# V0p2_Main_PCB2.net
KiCad netlist of a schematic drawn in EAGLE
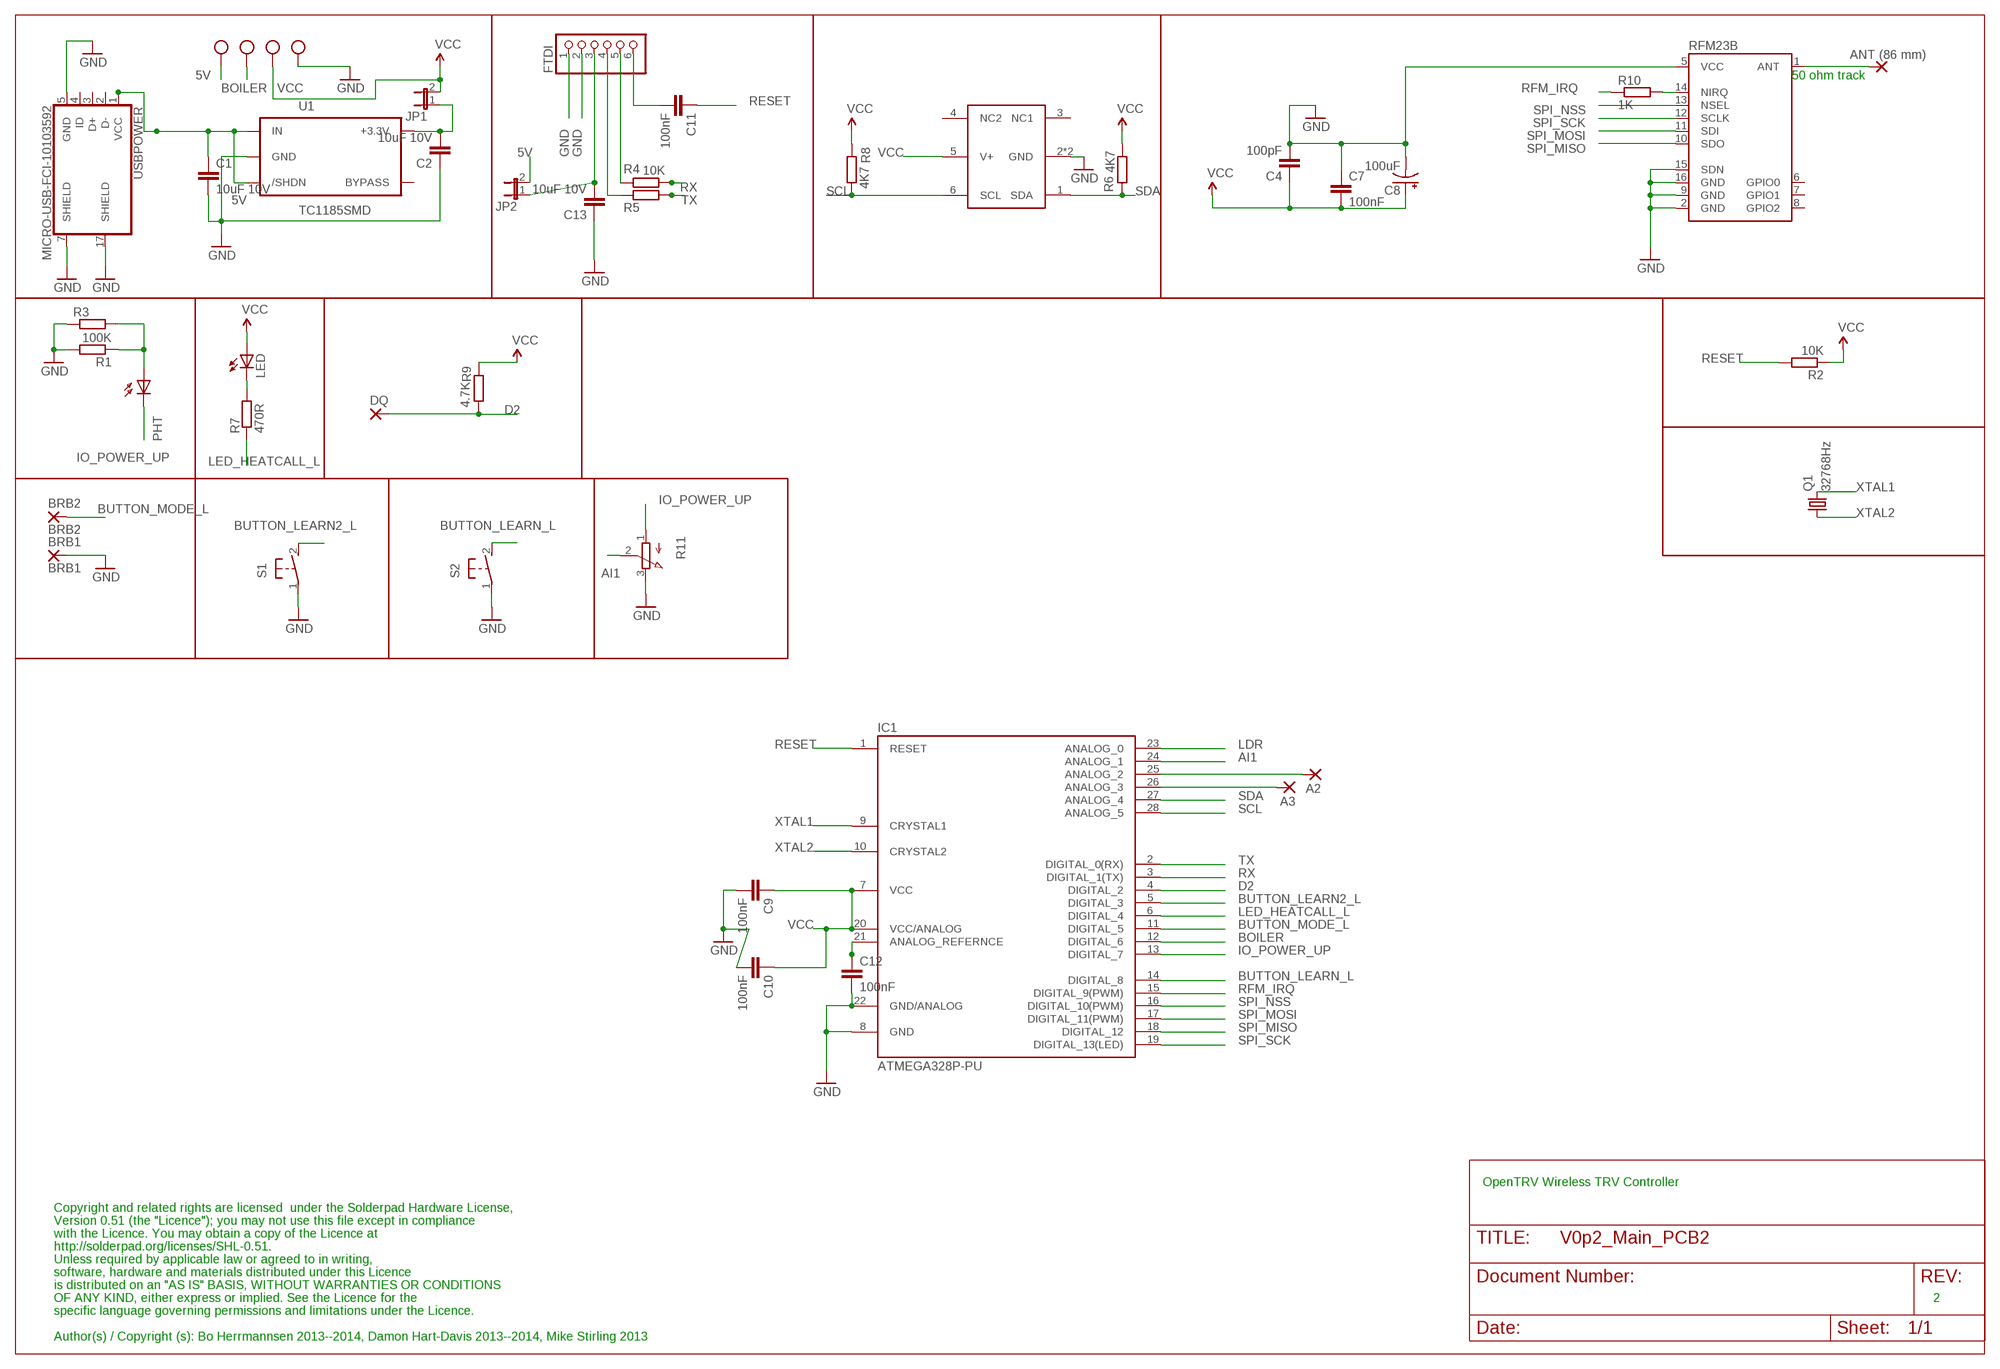
[diagram p0: schematic, sheet 1]

(export (version "E")
  (design (tool "Eeschema 10.0.6"))
  (components
    (comp (ref "A2")
      (value "2,15/1,0")
      (footprint "eagle-import:2,15_1,0")
      (libsource (lib "eagle-import") (part "2,15/1,0"))
    )
    (comp (ref "A3")
      (value "2,15/1,0")
      (footprint "eagle-import:2,15_1,0")
      (libsource (lib "eagle-import") (part "2,15/1,0"))
    )
    (comp (ref "ANT1")
      (value "ANT (86 mm)")
      (footprint "eagle-import:2,15_1,0")
      (libsource (lib "eagle-import") (part "2,15/1,0"))
    )
    (comp (ref "BRB1")
      (value "BRB1")
      (footprint "eagle-import:2,15_1,0")
      (libsource (lib "eagle-import") (part "2,15/1,0"))
    )
    (comp (ref "BRB2")
      (value "BRB2")
      (footprint "eagle-import:2,15_1,0")
      (libsource (lib "eagle-import") (part "2,15/1,0"))
    )
    (comp (ref "C1")
      (value "10uF 10V")
      (footprint "eagle-import:C0603")
      (libsource (lib "eagle-import") (part "C-EUC0603"))
    )
    (comp (ref "C2")
      (value "10uF 10V")
      (footprint "eagle-import:C0603")
      (libsource (lib "eagle-import") (part "C-EUC0603"))
    )
    (comp (ref "C4")
      (value "100pF")
      (footprint "eagle-import:C0603")
      (libsource (lib "eagle-import") (part "C-EUC0603"))
    )
    (comp (ref "C7")
      (value "100nF")
      (footprint "eagle-import:C0603")
      (libsource (lib "eagle-import") (part "C-EUC0603"))
    )
    (comp (ref "C8")
      (value "100uF")
      (footprint "eagle-import:EIA3216")
      (libsource (lib "eagle-import") (part "CAP_POL1206"))
    )
    (comp (ref "C9")
      (value "100nF")
      (footprint "eagle-import:C0603")
      (libsource (lib "eagle-import") (part "C-EUC0603"))
    )
    (comp (ref "C10")
      (value "100nF")
      (footprint "eagle-import:C0603")
      (libsource (lib "eagle-import") (part "C-EUC0603"))
    )
    (comp (ref "C11")
      (value "100nF")
      (footprint "eagle-import:C0603")
      (libsource (lib "eagle-import") (part "C-EUC0603"))
    )
    (comp (ref "C12")
      (value "100nF")
      (footprint "eagle-import:C0603")
      (libsource (lib "eagle-import") (part "C-EUC0603"))
    )
    (comp (ref "C13")
      (value "10uF 10V")
      (footprint "eagle-import:C0603")
      (libsource (lib "eagle-import") (part "C-EUC0603"))
    )
    (comp (ref "DQ")
      (value "2,15/1,0")
      (footprint "eagle-import:2,15_1,0")
      (libsource (lib "eagle-import") (part "2,15/1,0"))
    )
    (comp (ref "FTDI")
      (value "PINHD-1X6/90")
      (footprint "eagle-import:1X06_90")
      (libsource (lib "eagle-import") (part "PINHD-1X6/90"))
    )
    (comp (ref "IC1")
      (value "ATMEGA328P-PU")
      (footprint "eagle-import:DIL28-3")
      (libsource (lib "eagle-import") (part "ATMEGA8-PU"))
    )
    (comp (ref "JP1")
      (value "JP1E")
      (footprint "eagle-import:JP1")
      (libsource (lib "eagle-import") (part "JP1E"))
    )
    (comp (ref "JP2")
      (value "JP1E")
      (footprint "eagle-import:JP1")
      (libsource (lib "eagle-import") (part "JP1E"))
    )
    (comp (ref "LED")
      (value "LED3MM")
      (footprint "eagle-import:LED3MM")
      (libsource (lib "eagle-import") (part "LED3MM"))
    )
    (comp (ref "PHT")
      (value "BPX65")
      (footprint "eagle-import:BPX65")
      (fields (field (name "MPN") "BPX65."))
      (libsource (lib "eagle-import") (part "BPX65"))
    )
    (comp (ref "Q1")
      (value "32768Hz")
      (footprint "eagle-import:MC-306")
      (fields (field (name "MPN") "MC-306 60.0KHZ  100PPM ,12.5PF"))
      (libsource (lib "eagle-import") (part "MC-306"))
    )
    (comp (ref "R1")
      (value "100K")
      (footprint "eagle-import:R0603")
      (libsource (lib "eagle-import") (part "R-EU_R0603"))
    )
    (comp (ref "R2")
      (value "10K")
      (footprint "eagle-import:R0603")
      (libsource (lib "eagle-import") (part "R-EU_R0603"))
    )
    (comp (ref "R3")
      (value "R-EU_0309/V")
      (footprint "eagle-import:0309V")
      (libsource (lib "eagle-import") (part "R-EU_0309/V"))
    )
    (comp (ref "R4")
      (value "10K")
      (footprint "eagle-import:R0603")
      (libsource (lib "eagle-import") (part "R-EU_R0603"))
    )
    (comp (ref "R5")
      (value "10K")
      (footprint "eagle-import:R0603")
      (libsource (lib "eagle-import") (part "R-EU_R0603"))
    )
    (comp (ref "R6")
      (value "4K7")
      (footprint "eagle-import:R0603")
      (libsource (lib "eagle-import") (part "R-EU_R0603"))
    )
    (comp (ref "R7")
      (value "470R")
      (footprint "eagle-import:R0603")
      (libsource (lib "eagle-import") (part "R-EU_R0603"))
    )
    (comp (ref "R8")
      (value "4K7")
      (footprint "eagle-import:R0603")
      (libsource (lib "eagle-import") (part "R-EU_R0603"))
    )
    (comp (ref "R9")
      (value "4.7K")
      (footprint "eagle-import:R0603")
      (libsource (lib "eagle-import") (part "R-EU_R0603"))
    )
    (comp (ref "R10")
      (value "1K")
      (footprint "eagle-import:R0603")
      (libsource (lib "eagle-import") (part "R-EU_R0603"))
    )
    (comp (ref "R11")
      (value "EVUE2A")
      (footprint "eagle-import:EVUE")
      (libsource (lib "eagle-import") (part "EVUE2A"))
    )
    (comp (ref "RFM23B")
      (value "RFM23B")
      (footprint "eagle-import:RFM23-XXX-S1")
      (libsource (lib "eagle-import") (part "RFM23B"))
    )
    (comp (ref "S1")
      (value "31-XX")
      (footprint "eagle-import:B3F-31XX")
      (libsource (lib "eagle-import") (part "31-XX"))
    )
    (comp (ref "S2")
      (value "31-XX")
      (footprint "eagle-import:B3F-31XX")
      (libsource (lib "eagle-import") (part "31-XX"))
    )
    (comp (ref "U$4")
      (value "SHT21")
      (footprint "eagle-import:SHT21")
      (libsource (lib "eagle-import") (part "SHT21"))
    )
    (comp (ref "U1")
      (value "TC1185SMD")
      (footprint "eagle-import:TC1185")
      (libsource (lib "eagle-import") (part "TC1185SMD"))
    )
    (comp (ref "USBPOWER")
      (value "MICRO-USB-FCI-10103592")
      (footprint "eagle-import:MICRO-USB-FCI-10103592")
      (libsource (lib "eagle-import") (part "MICRO-USB-FCI-10103592"))
    )
    (comp (ref "X1")
      (value "W237-102")
      (footprint "eagle-import:SCREWTERMINAL")
      (fields (field (name "MPN") "237-102"))
      (libsource (lib "eagle-import") (part "W237-102"))
    )
    (comp (ref "X2")
      (value "W237-102")
      (footprint "eagle-import:SCREWTERMINAL")
      (fields (field (name "MPN") "237-102"))
      (libsource (lib "eagle-import") (part "W237-102"))
    )
  )
  (nets
    (net (code "1") (name "/5V") (class "Default")
      (node (ref "C1") (pin "1") (pinfunction "1_1") (pintype "passive"))
      (node (ref "JP2") (pin "2") (pinfunction "2_2") (pintype "passive"))
      (node (ref "U1") (pin "1") (pinfunction "IN_1") (pintype "passive"))
      (node (ref "U1") (pin "3") (pinfunction "/SHDN_3") (pintype "passive"))
      (node (ref "USBPOWER") (pin "1") (pinfunction "VCC_1") (pintype "bidirectional"))
      (node (ref "X1") (pin "2") (pinfunction "KL_2") (pintype "passive"))
    )
    (net (code "2") (name "/AI1") (class "Default")
      (node (ref "IC1") (pin "24") (pinfunction "ANALOG_1_24") (pintype "bidirectional"))
      (node (ref "R11") (pin "2") (pinfunction "S_2") (pintype "passive"))
    )
    (net (code "3") (name "/BOILER") (class "Default")
      (node (ref "IC1") (pin "12") (pinfunction "DIGITAL_6_12") (pintype "bidirectional"))
      (node (ref "X1") (pin "1") (pinfunction "KL_1") (pintype "passive"))
    )
    (net (code "4") (name "/BUTTON_LEARN2_L") (class "Default")
      (node (ref "IC1") (pin "5") (pinfunction "DIGITAL_3_5") (pintype "bidirectional"))
      (node (ref "S1") (pin "2") (pinfunction "S_2") (pintype "passive"))
    )
    (net (code "5") (name "/BUTTON_LEARN_L") (class "Default")
      (node (ref "IC1") (pin "14") (pinfunction "DIGITAL_8_14") (pintype "bidirectional"))
      (node (ref "S2") (pin "2") (pinfunction "S_2") (pintype "passive"))
    )
    (net (code "6") (name "/BUTTON_MODE_L") (class "Default")
      (node (ref "BRB2") (pin "1") (pinfunction "P_1") (pintype "passive"))
      (node (ref "IC1") (pin "11") (pinfunction "DIGITAL_5_11") (pintype "bidirectional"))
    )
    (net (code "7") (name "/D2") (class "Default")
      (node (ref "DQ") (pin "1") (pinfunction "P_1") (pintype "passive"))
      (node (ref "IC1") (pin "4") (pinfunction "DIGITAL_2_4") (pintype "bidirectional"))
      (node (ref "R9") (pin "1") (pinfunction "1_1") (pintype "passive"))
    )
    (net (code "8") (name "/IO_POWER_UP") (class "Default")
      (node (ref "IC1") (pin "13") (pinfunction "DIGITAL_7_13") (pintype "bidirectional"))
      (node (ref "PHT") (pin "K") (pinfunction "C_K") (pintype "passive"))
      (node (ref "R11") (pin "1") (pinfunction "A_1") (pintype "passive"))
    )
    (net (code "9") (name "/LDR") (class "Default")
      (node (ref "IC1") (pin "23") (pinfunction "ANALOG_0_23") (pintype "bidirectional"))
      (node (ref "PHT") (pin "A") (pinfunction "A_A") (pintype "passive"))
      (node (ref "R1") (pin "1") (pinfunction "1_1") (pintype "passive"))
      (node (ref "R3") (pin "2") (pinfunction "2_2") (pintype "passive"))
    )
    (net (code "10") (name "/LED_HEATCALL_L") (class "Default")
      (node (ref "IC1") (pin "6") (pinfunction "DIGITAL_4_6") (pintype "bidirectional"))
      (node (ref "R7") (pin "1") (pinfunction "1_1") (pintype "passive"))
    )
    (net (code "11") (name "/RESET") (class "Default")
      (node (ref "C11") (pin "1") (pinfunction "1_1") (pintype "passive"))
      (node (ref "IC1") (pin "1") (pinfunction "RESET_1") (pintype "bidirectional"))
      (node (ref "R2") (pin "2") (pinfunction "2_2") (pintype "passive"))
    )
    (net (code "12") (name "/RFM_IRQ") (class "Default")
      (node (ref "IC1") (pin "15") (pinfunction "DIGITAL_9(PWM)_15") (pintype "bidirectional"))
      (node (ref "R10") (pin "1") (pinfunction "1_1") (pintype "passive"))
    )
    (net (code "13") (name "/RX") (class "Default")
      (node (ref "IC1") (pin "3") (pinfunction "DIGITAL_1(TX)_3") (pintype "bidirectional"))
      (node (ref "R4") (pin "1") (pinfunction "1_1") (pintype "passive"))
    )
    (net (code "14") (name "/SCL") (class "Default")
      (node (ref "IC1") (pin "28") (pinfunction "ANALOG_5_28") (pintype "bidirectional"))
      (node (ref "R8") (pin "1") (pinfunction "1_1") (pintype "passive"))
      (node (ref "U$4") (pin "6") (pinfunction "SCL_6") (pintype "bidirectional"))
    )
    (net (code "15") (name "/SDA") (class "Default")
      (node (ref "IC1") (pin "27") (pinfunction "ANALOG_4_27") (pintype "bidirectional"))
      (node (ref "R6") (pin "2") (pinfunction "2_2") (pintype "passive"))
      (node (ref "U$4") (pin "1") (pinfunction "SDA_1") (pintype "bidirectional"))
    )
    (net (code "16") (name "/SPI_MISO") (class "Default")
      (node (ref "IC1") (pin "18") (pinfunction "DIGITAL_12_18") (pintype "bidirectional"))
      (node (ref "RFM23B") (pin "10") (pinfunction "SDO_10") (pintype "output"))
    )
    (net (code "17") (name "/SPI_MOSI") (class "Default")
      (node (ref "IC1") (pin "17") (pinfunction "DIGITAL_11(PWM)_17") (pintype "bidirectional"))
      (node (ref "RFM23B") (pin "11") (pinfunction "SDI_11") (pintype "input"))
    )
    (net (code "18") (name "/SPI_NSS") (class "Default")
      (node (ref "IC1") (pin "16") (pinfunction "DIGITAL_10(PWM)_16") (pintype "bidirectional"))
      (node (ref "RFM23B") (pin "13") (pinfunction "NSEL_13") (pintype "input"))
    )
    (net (code "19") (name "/SPI_SCK") (class "Default")
      (node (ref "IC1") (pin "19") (pinfunction "DIGITAL_13(LED)_19") (pintype "bidirectional"))
      (node (ref "RFM23B") (pin "12") (pinfunction "SCLK_12") (pintype "input"))
    )
    (net (code "20") (name "/TX") (class "Default")
      (node (ref "IC1") (pin "2") (pinfunction "DIGITAL_0(RX)_2") (pintype "bidirectional"))
      (node (ref "R5") (pin "1") (pinfunction "1_1") (pintype "passive"))
    )
    (net (code "21") (name "/XTAL1") (class "Default")
      (node (ref "IC1") (pin "9") (pinfunction "CRYSTAL1_9") (pintype "bidirectional"))
      (node (ref "Q1") (pin "4") (pinfunction "2_4") (pintype "passive"))
    )
    (net (code "22") (name "/XTAL2") (class "Default")
      (node (ref "IC1") (pin "10") (pinfunction "CRYSTAL2_10") (pintype "bidirectional"))
      (node (ref "Q1") (pin "1") (pinfunction "1_1") (pintype "passive"))
    )
    (net (code "23") (name "GND") (class "Default")
      (node (ref "BRB1") (pin "1") (pinfunction "P_1") (pintype "passive"))
      (node (ref "C1") (pin "2") (pinfunction "2_2") (pintype "passive"))
      (node (ref "C10") (pin "2") (pinfunction "2_2") (pintype "passive"))
      (node (ref "C12") (pin "2") (pinfunction "2_2") (pintype "passive"))
      (node (ref "C13") (pin "1") (pinfunction "1_1") (pintype "passive"))
      (node (ref "C2") (pin "1") (pinfunction "1_1") (pintype "passive"))
      (node (ref "C4") (pin "2") (pinfunction "2_2") (pintype "passive"))
      (node (ref "C7") (pin "1") (pinfunction "1_1") (pintype "passive"))
      (node (ref "C8") (pin "C") (pinfunction "-_C") (pintype "passive"))
      (node (ref "C9") (pin "2") (pinfunction "2_2") (pintype "passive"))
      (node (ref "FTDI") (pin "1") (pinfunction "1_1") (pintype "passive"))
      (node (ref "FTDI") (pin "2") (pinfunction "2_2") (pintype "passive"))
      (node (ref "IC1") (pin "22") (pinfunction "GND/ANALOG_22") (pintype "power_in"))
      (node (ref "IC1") (pin "8") (pinfunction "GND_8") (pintype "power_in"))
      (node (ref "R1") (pin "2") (pinfunction "2_2") (pintype "passive"))
      (node (ref "R11") (pin "3") (pinfunction "E_3") (pintype "passive"))
      (node (ref "R3") (pin "1") (pinfunction "1_1") (pintype "passive"))
      (node (ref "RFM23B") (pin "15") (pinfunction "SDN_15") (pintype "input"))
      (node (ref "RFM23B") (pin "16") (pinfunction "GND_16") (pintype "power_in"))
      (node (ref "RFM23B") (pin "2") (pinfunction "GND_2") (pintype "power_in"))
      (node (ref "RFM23B") (pin "5") (pinfunction "VCC_5") (pintype "bidirectional"))
      (node (ref "RFM23B") (pin "9") (pinfunction "GND_9") (pintype "power_in"))
      (node (ref "S1") (pin "1") (pinfunction "P_1") (pintype "passive"))
      (node (ref "S2") (pin "1") (pinfunction "P_1") (pintype "passive"))
      (node (ref "U$4") (pin "2") (pinfunction "GND_2") (pintype "bidirectional"))
      (node (ref "U$4") (pin "P$1") (pinfunction "GND_P$1") (pintype "bidirectional"))
      (node (ref "U1") (pin "2") (pinfunction "GND_2") (pintype "passive"))
      (node (ref "USBPOWER") (pin "17") (pinfunction "SHIELD_17") (pintype "bidirectional"))
      (node (ref "USBPOWER") (pin "5") (pinfunction "GND_5") (pintype "bidirectional"))
      (node (ref "USBPOWER") (pin "7") (pinfunction "SHIELD_7") (pintype "bidirectional"))
      (node (ref "X2") (pin "2") (pinfunction "KL_2") (pintype "passive"))
    )
    (net (code "24") (name "Net-(A2-P)") (class "Default")
      (node (ref "A2") (pin "1") (pinfunction "P_1") (pintype "passive"))
      (node (ref "IC1") (pin "25") (pinfunction "ANALOG_2_25") (pintype "bidirectional"))
    )
    (net (code "25") (name "Net-(A3-P)") (class "Default")
      (node (ref "A3") (pin "1") (pinfunction "P_1") (pintype "passive"))
      (node (ref "IC1") (pin "26") (pinfunction "ANALOG_3_26") (pintype "bidirectional"))
    )
    (net (code "26") (name "Net-(ANT1-P)") (class "Default")
      (node (ref "ANT1") (pin "1") (pinfunction "P_1") (pintype "passive"))
      (node (ref "RFM23B") (pin "1") (pinfunction "ANT_1") (pintype "bidirectional"))
    )
    (net (code "27") (name "Net-(C11-Pad2)") (class "Default")
      (node (ref "C11") (pin "2") (pinfunction "2_2") (pintype "passive"))
      (node (ref "FTDI") (pin "6") (pinfunction "6_6") (pintype "passive"))
    )
    (net (code "28") (name "Net-(C13-Pad2)") (class "Default")
      (node (ref "C13") (pin "2") (pinfunction "2_2") (pintype "passive"))
      (node (ref "FTDI") (pin "3") (pinfunction "3_3") (pintype "passive"))
      (node (ref "JP2") (pin "1") (pinfunction "1_1") (pintype "passive"))
    )
    (net (code "29") (name "Net-(FTDI-Pad4)") (class "Default")
      (node (ref "FTDI") (pin "4") (pinfunction "4_4") (pintype "passive"))
      (node (ref "R5") (pin "2") (pinfunction "2_2") (pintype "passive"))
    )
    (net (code "30") (name "Net-(FTDI-Pad5)") (class "Default")
      (node (ref "FTDI") (pin "5") (pinfunction "5_5") (pintype "passive"))
      (node (ref "R4") (pin "2") (pinfunction "2_2") (pintype "passive"))
    )
    (net (code "31") (name "Net-(IC1-ANALOG_REFERNCE)") (class "Default")
      (node (ref "C12") (pin "1") (pinfunction "1_1") (pintype "passive"))
      (node (ref "IC1") (pin "21") (pinfunction "ANALOG_REFERNCE_21") (pintype "passive"))
    )
    (net (code "32") (name "Net-(LED-C)") (class "Default")
      (node (ref "LED") (pin "K") (pinfunction "C_K") (pintype "passive"))
      (node (ref "R7") (pin "2") (pinfunction "2_2") (pintype "passive"))
    )
    (net (code "33") (name "Net-(RFM23B-NIRQ)") (class "Default")
      (node (ref "R10") (pin "2") (pinfunction "2_2") (pintype "passive"))
      (node (ref "RFM23B") (pin "14") (pinfunction "NIRQ_14") (pintype "output"))
    )
    (net (code "34") (name "Net-(U1-+3.3V)") (class "Default")
      (node (ref "C2") (pin "2") (pinfunction "2_2") (pintype "passive"))
      (node (ref "JP1") (pin "1") (pinfunction "1_1") (pintype "passive"))
      (node (ref "U1") (pin "5") (pinfunction "+3.3V_5") (pintype "power_in"))
    )
    (net (code "35") (name "VCC") (class "Default")
      (node (ref "C10") (pin "1") (pinfunction "1_1") (pintype "passive"))
      (node (ref "C4") (pin "1") (pinfunction "1_1") (pintype "passive"))
      (node (ref "C7") (pin "2") (pinfunction "2_2") (pintype "passive"))
      (node (ref "C8") (pin "A") (pinfunction "+_A") (pintype "passive"))
      (node (ref "C9") (pin "1") (pinfunction "1_1") (pintype "passive"))
      (node (ref "IC1") (pin "20") (pinfunction "VCC/ANALOG_20") (pintype "passive"))
      (node (ref "IC1") (pin "7") (pinfunction "VCC_7") (pintype "power_in"))
      (node (ref "JP1") (pin "2") (pinfunction "2_2") (pintype "passive"))
      (node (ref "LED") (pin "A") (pinfunction "A_A") (pintype "passive"))
      (node (ref "R2") (pin "1") (pinfunction "1_1") (pintype "passive"))
      (node (ref "R6") (pin "1") (pinfunction "1_1") (pintype "passive"))
      (node (ref "R8") (pin "2") (pinfunction "2_2") (pintype "passive"))
      (node (ref "R9") (pin "2") (pinfunction "2_2") (pintype "passive"))
      (node (ref "U$4") (pin "5") (pinfunction "V+_5") (pintype "bidirectional"))
      (node (ref "X2") (pin "1") (pinfunction "KL_1") (pintype "passive"))
    )
    (net (code "36") (name "unconnected-(RFM23B-GPIO0-Pad6)") (class "Default")
      (node (ref "RFM23B") (pin "6") (pinfunction "GPIO0_6") (pintype "bidirectional"))
    )
    (net (code "37") (name "unconnected-(RFM23B-GPIO1-Pad7)") (class "Default")
      (node (ref "RFM23B") (pin "7") (pinfunction "GPIO1_7") (pintype "bidirectional"))
    )
    (net (code "38") (name "unconnected-(RFM23B-GPIO2-Pad8)") (class "Default")
      (node (ref "RFM23B") (pin "8") (pinfunction "GPIO2_8") (pintype "bidirectional"))
    )
    (net (code "39") (name "unconnected-(U$4-NC1-Pad3)") (class "Default")
      (node (ref "U$4") (pin "3") (pinfunction "NC1_3") (pintype "bidirectional"))
    )
    (net (code "40") (name "unconnected-(U$4-NC2-Pad4)") (class "Default")
      (node (ref "U$4") (pin "4") (pinfunction "NC2_4") (pintype "bidirectional"))
    )
    (net (code "41") (name "unconnected-(U1-BYPASS-Pad4)") (class "Default")
      (node (ref "U1") (pin "4") (pinfunction "BYPASS_4") (pintype "passive"))
    )
    (net (code "42") (name "unconnected-(USBPOWER-D+-Pad3)") (class "Default")
      (node (ref "USBPOWER") (pin "3") (pinfunction "D+_3") (pintype "bidirectional"))
    )
    (net (code "43") (name "unconnected-(USBPOWER-D--Pad2)") (class "Default")
      (node (ref "USBPOWER") (pin "2") (pinfunction "D-_2") (pintype "bidirectional"))
    )
    (net (code "44") (name "unconnected-(USBPOWER-ID-Pad4)") (class "Default")
      (node (ref "USBPOWER") (pin "4") (pinfunction "ID_4") (pintype "bidirectional"))
    )
  )
)
